# RS485.net
KiCad netlist of a schematic drawn in Altium Designer
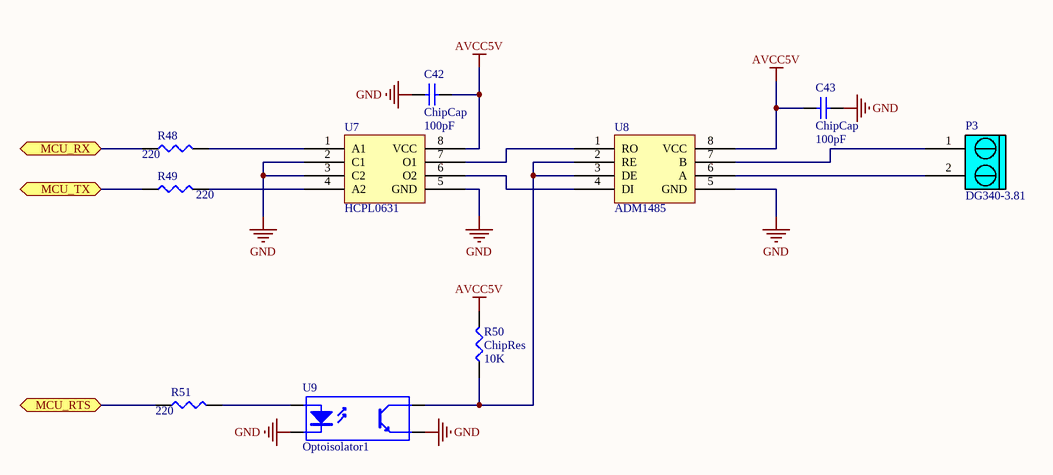
[diagram p0: RS485.SchDoc]

(export (version "E")
  (design (tool "Eeschema 10.0.6"))
  (components
    (comp (ref "C42")
      (value "ChipCap")
      (footprint "CAP0805")
      (description "Capacitor")
      (fields (field (name "ALTIUM_VALUE") "100pF") (field (name "PUBLISHER") "Altium Limited"))
      (libsource (lib "Common Devices") (part "ChipCap"))
    )
    (comp (ref "C43")
      (value "ChipCap")
      (footprint "CAP0805")
      (description "Capacitor")
      (fields (field (name "ALTIUM_VALUE") "100pF") (field (name "PUBLISHER") "Altium Limited"))
      (libsource (lib "Common Devices") (part "ChipCap"))
    )
    (comp (ref "P3")
      (value "DG340-3.81")
      (footprint "DG340-3.81-02P-00A(H)")
      (description "Terminal block")
      (libsource (lib "Connectors") (part "DG340-3.81-02P"))
    )
    (comp (ref "R48")
      (value "220")
      (footprint "RES0805")
      (description "Chip resistor")
      (fields (field (name "Comment") "ChipRes"))
      (libsource (lib "Common Devices") (part "ChipRes"))
    )
    (comp (ref "R49")
      (value "220")
      (footprint "RES0805")
      (description "Chip resistor")
      (fields (field (name "Comment") "ChipRes"))
      (libsource (lib "Common Devices") (part "ChipRes"))
    )
    (comp (ref "R50")
      (value "ChipRes")
      (footprint "RES0805")
      (description "Chip resistor")
      (fields (field (name "ALTIUM_VALUE") "10K"))
      (libsource (lib "Common Devices") (part "ChipRes"))
    )
    (comp (ref "R51")
      (value "220")
      (footprint "RES0805")
      (description "Chip resistor")
      (fields (field (name "Comment") "ChipRes"))
      (libsource (lib "Common Devices") (part "ChipRes"))
    )
    (comp (ref "U7")
      (value "HCPL0631")
      (footprint "SOIC8")
      (description "2-channel opto-coupler")
      (libsource (lib "Avago Optocouplers") (part "HCPL0631"))
    )
    (comp (ref "U8")
      (value "ADM1485")
      (footprint "SO-8_L")
      (description "5 V Low Power  EIA RS-485 Transceiver")
      (libsource (lib "Analog Devices AD converter") (part "ADM1485"))
    )
    (comp (ref "U9")
      (value "Optoisolator1")
      (footprint "DIP-4")
      (description "4-Pin Phototransistor Optocoupler")
      (fields (field (name "PUBLISHER") "Altium Limited"))
      (libsource (lib "Miscellaneous Devices") (part "Optoisolator1"))
    )
  )
  (nets
    (net (code "1") (name "/MCU_RTS") (class "Default") (node (ref "R51") (pin "1") (pintype "passive")))
    (net (code "2") (name "/MCU_RX") (class "Default") (node (ref "R48") (pin "1") (pintype "passive")))
    (net (code "3") (name "/MCU_TX") (class "Default") (node (ref "R49") (pin "1") (pintype "passive")))
    (net (code "4") (name "AVCC5V") (class "Default")
      (node (ref "C42") (pin "2") (pinfunction "2_2") (pintype "passive"))
      (node (ref "C43") (pin "1") (pinfunction "1_1") (pintype "passive"))
      (node (ref "R50") (pin "2") (pintype "passive"))
      (node (ref "U7") (pin "8") (pinfunction "VCC_8") (pintype "passive"))
      (node (ref "U8") (pin "8") (pinfunction "VCC_8") (pintype "passive"))
    )
    (net (code "5") (name "GND") (class "Default")
      (node (ref "C42") (pin "1") (pinfunction "1_1") (pintype "passive"))
      (node (ref "C43") (pin "2") (pinfunction "2_2") (pintype "passive"))
      (node (ref "U7") (pin "2") (pinfunction "C1_2") (pintype "passive"))
      (node (ref "U7") (pin "3") (pinfunction "C2_3") (pintype "passive"))
      (node (ref "U7") (pin "5") (pinfunction "GND_5") (pintype "passive"))
      (node (ref "U8") (pin "5") (pinfunction "GND_5") (pintype "passive"))
      (node (ref "U9") (pin "2") (pinfunction "K_2") (pintype "passive"))
      (node (ref "U9") (pin "3") (pinfunction "E_3") (pintype "passive"))
    )
    (net (code "6") (name "Net-(U7-A1)") (class "Default")
      (node (ref "R48") (pin "2") (pintype "passive"))
      (node (ref "U7") (pin "1") (pinfunction "A1_1") (pintype "passive"))
    )
    (net (code "7") (name "Net-(U7-A2)") (class "Default")
      (node (ref "R49") (pin "2") (pintype "passive"))
      (node (ref "U7") (pin "4") (pinfunction "A2_4") (pintype "passive"))
    )
    (net (code "8") (name "Net-(U7-O1)") (class "Default")
      (node (ref "U7") (pin "7") (pinfunction "O1_7") (pintype "passive"))
      (node (ref "U8") (pin "1") (pinfunction "RO_1") (pintype "passive"))
    )
    (net (code "9") (name "Net-(U7-O2)") (class "Default")
      (node (ref "U7") (pin "6") (pinfunction "O2_6") (pintype "passive"))
      (node (ref "U8") (pin "4") (pinfunction "DI_4") (pintype "passive"))
    )
    (net (code "10") (name "Net-(U8-A)") (class "Default")
      (node (ref "P3") (pin "2") (pinfunction "2_2") (pintype "passive"))
      (node (ref "U8") (pin "6") (pinfunction "A_6") (pintype "passive"))
    )
    (net (code "11") (name "Net-(U8-B)") (class "Default")
      (node (ref "P3") (pin "1") (pinfunction "1_1") (pintype "passive"))
      (node (ref "U8") (pin "7") (pinfunction "B_7") (pintype "passive"))
    )
    (net (code "12") (name "Net-(U8-DE)") (class "Default")
      (node (ref "R50") (pin "1") (pintype "passive"))
      (node (ref "U8") (pin "2") (pinfunction "RE_2") (pintype "passive"))
      (node (ref "U8") (pin "3") (pinfunction "DE_3") (pintype "passive"))
      (node (ref "U9") (pin "4") (pinfunction "C_4") (pintype "passive"))
    )
    (net (code "13") (name "Net-(U9-A)") (class "Default")
      (node (ref "R51") (pin "2") (pintype "passive"))
      (node (ref "U9") (pin "1") (pinfunction "A_1") (pintype "passive"))
    )
  )
)
